# GAN_Synchronous_Buck.net
KiCad netlist of a schematic drawn in Altium Designer
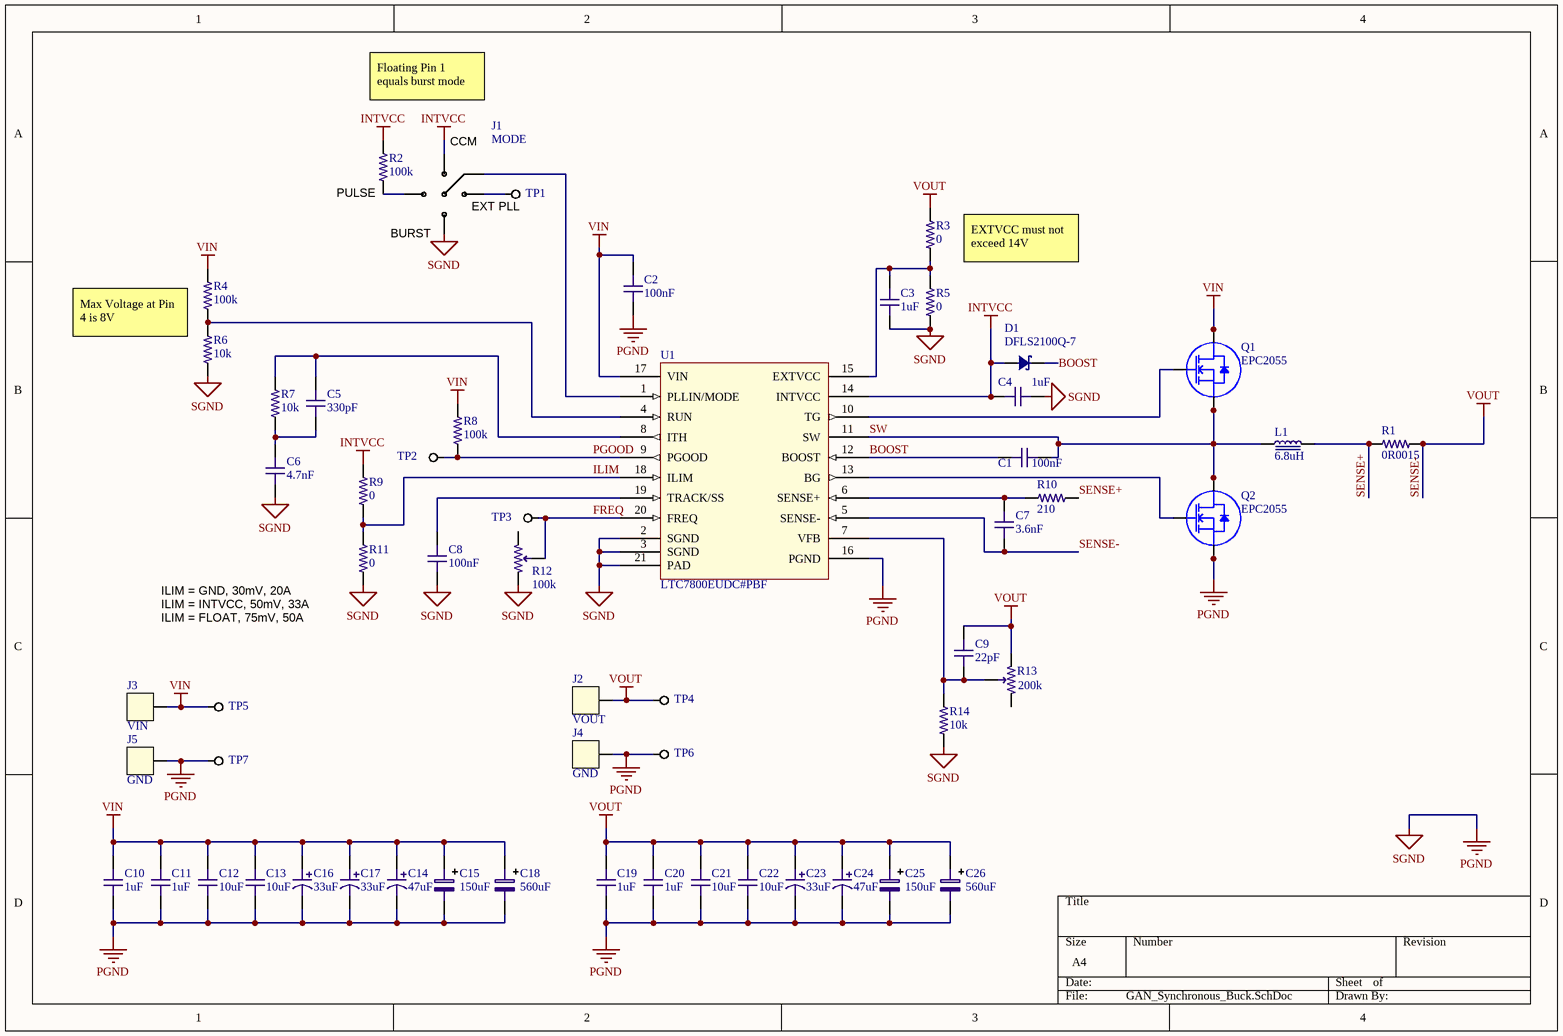
[diagram p0: GAN_Synchronous_Buck.SchDoc]

(export (version "E")
  (design (tool "Eeschema 10.0.6"))
  (components
    (comp (ref "C1")
      (value "100nF")
      (footprint "C0603-IPC")
      (description "CAP CER 0.1UF 50V X7R 0603")
      (fields (field (name "Comment") "C0603 100nF 50V X7R"))
      (libsource (lib "Capacitors") (part "C0603 100nF 50V X7R"))
    )
    (comp (ref "C2")
      (value "100nF")
      (footprint "C0603-IPC")
      (description "CAP CER 0.1UF 50V X7R 0603")
      (fields (field (name "Comment") "C0603 100nF 50V X7R"))
      (libsource (lib "Capacitors") (part "C0603 100nF 50V X7R"))
    )
    (comp (ref "C3")
      (value "1uF")
      (footprint "C0603-IPC")
      (description "CAP CER 1UF 50V X7R 0603")
      (fields (field (name "Comment") "C0603 1uF 50V X7R"))
      (libsource (lib "Capacitors") (part "C0603 1uF 50V X7R"))
    )
    (comp (ref "C4")
      (value "1uF")
      (footprint "C0603-IPC")
      (description "CAP CER 1UF 50V X7R 0603")
      (fields (field (name "Comment") "C0603 1uF 50V X7R"))
      (libsource (lib "Capacitors") (part "C0603 1uF 50V X7R"))
    )
    (comp (ref "C5")
      (value "330pF")
      (footprint "C0603-IPC")
      (description "CAP CER 330PF 50V C0G/NP0 0603")
      (fields (field (name "Comment") "C0603 330pF 50V C0G"))
      (libsource (lib "Capacitors") (part "C0603 330pF 50V C0G"))
    )
    (comp (ref "C6")
      (value "4.7nF")
      (footprint "C0603-IPC")
      (description "CAP CER 4700PF 50V X7R 0603")
      (fields (field (name "Comment") "C0603 4.7nF 50V X7R"))
      (libsource (lib "Capacitors") (part "C0603 4.7nF 50V X7R"))
    )
    (comp (ref "C7")
      (value "3.6nF")
      (footprint "C0603-IPC")
      (description "Chip Capacitor, 0603, 3.6nF, 50V, X7R")
      (fields (field (name "Comment") "C0603 3.6nF 50V C0G"))
      (libsource (lib "Capacitors") (part "C0603 3.6nF 50V C0G"))
    )
    (comp (ref "C8")
      (value "100nF")
      (footprint "C0603-IPC")
      (description "CAP CER 0.1UF 50V X7R 0603")
      (fields (field (name "Comment") "C0603 100nF 50V X7R"))
      (libsource (lib "Capacitors") (part "C0603 100nF 50V X7R"))
    )
    (comp (ref "C9")
      (value "22pF")
      (footprint "C0603-IPC")
      (description "CAP CER 22PF 50V C0G/NP0 0603")
      (fields (field (name "Comment") "C0603 22pF 50V C0G"))
      (libsource (lib "Capacitors") (part "C0603 22pF 50V C0G"))
    )
    (comp (ref "C10")
      (value "1uF")
      (footprint "C0603-IPC")
      (description "CAP CER 1UF 50V X7R 0603")
      (fields (field (name "Comment") "C0603 1uF 50V X7R"))
      (libsource (lib "Capacitors") (part "C0603 1uF 50V X7R"))
    )
    (comp (ref "C11")
      (value "1uF")
      (footprint "C0603-IPC")
      (description "CAP CER 1UF 50V X7R 0603")
      (fields (field (name "Comment") "C0603 1uF 50V X7R"))
      (libsource (lib "Capacitors") (part "C0603 1uF 50V X7R"))
    )
    (comp (ref "C12")
      (value "10uF")
      (footprint "C1210-IPC")
      (description "Chip Capacitor, 1210, 10uF, 75V, X5R")
      (fields (field (name "Comment") "C1210 10uF 75V X5R"))
      (libsource (lib "Capacitors") (part "C1210 10uF 16V X5R"))
    )
    (comp (ref "C13")
      (value "10uF")
      (footprint "C1210-IPC")
      (description "Chip Capacitor, 1210, 10uF, 75V, X5R")
      (fields (field (name "Comment") "C1210 10uF 75V X5R"))
      (libsource (lib "Capacitors") (part "C1210 10uF 16V X5R"))
    )
    (comp (ref "C14")
      (value "47uF")
      (footprint "C-SMD-Polarized-6.3x7.7mm")
      (description "47uF ±20% 50V SMD,6.3x7.7mm Aluminum Electrolytic Capacitors - SMD")
      (fields (field (name "Comment") "UUR1H470MCL6GS"))
      (libsource (lib "Capacitors") (part "C-SMD 47uF 50V Electrolytic"))
    )
    (comp (ref "C15")
      (value "150uF")
      (footprint "C-POLARIZED-5-12.5")
      (fields (field (name "Comment") "35ZLH1000MEFC12.5X20"))
      (libsource (lib "Capacitors") (part "C-THT 1000uF 35V Electrolytic"))
    )
    (comp (ref "C16")
      (value "33uF")
      (footprint "C-SMD-Polarized-10x10.2mm")
      (description "33 µF 80 V Aluminum Electrolytic Capacitors Radial, Can - SMD 1Ohm @ 100kHz 2000 Hrs @ 125°C")
      (fields (field (name "VOLTAGE") "80V") (field (name "Comment") "PCE3675CT-ND"))
      (libsource (lib "Capacitors") (part "C-SMD 33uF 80V Electrolytic"))
    )
    (comp (ref "C17")
      (value "33uF")
      (footprint "C-SMD-Polarized-10x10.2mm")
      (description "33 µF 80 V Aluminum Electrolytic Capacitors Radial, Can - SMD 1Ohm @ 100kHz 2000 Hrs @ 125°C")
      (fields (field (name "VOLTAGE") "80V") (field (name "Comment") "PCE3675CT-ND"))
      (libsource (lib "Capacitors") (part "C-SMD 33uF 80V Electrolytic"))
    )
    (comp (ref "C18")
      (value "560uF")
      (footprint "C-POLARIZED-5-12.5")
      (fields (field (name "Comment") "35ZLH1000MEFC12.5X20"))
      (libsource (lib "Capacitors") (part "C-THT 1000uF 35V Electrolytic"))
    )
    (comp (ref "C19")
      (value "1uF")
      (footprint "C0603-IPC")
      (description "CAP CER 1UF 50V X7R 0603")
      (fields (field (name "Comment") "C0603 1uF 50V X7R"))
      (libsource (lib "Capacitors") (part "C0603 1uF 50V X7R"))
    )
    (comp (ref "C20")
      (value "1uF")
      (footprint "C0603-IPC")
      (description "CAP CER 1UF 50V X7R 0603")
      (fields (field (name "Comment") "C0603 1uF 50V X7R"))
      (libsource (lib "Capacitors") (part "C0603 1uF 50V X7R"))
    )
    (comp (ref "C21")
      (value "10uF")
      (footprint "C1210-IPC")
      (description "Chip Capacitor, 1210, 10uF, 75V, X5R")
      (fields (field (name "Comment") "C1210 10uF 75V X5R"))
      (libsource (lib "Capacitors") (part "C1210 10uF 16V X5R"))
    )
    (comp (ref "C22")
      (value "10uF")
      (footprint "C1210-IPC")
      (description "Chip Capacitor, 1210, 10uF, 75V, X5R")
      (fields (field (name "Comment") "C1210 10uF 75V X5R"))
      (libsource (lib "Capacitors") (part "C1210 10uF 16V X5R"))
    )
    (comp (ref "C23")
      (value "33uF")
      (footprint "C-SMD-Polarized-10x10.2mm")
      (description "33 µF 80 V Aluminum Electrolytic Capacitors Radial, Can - SMD 1Ohm @ 100kHz 2000 Hrs @ 125°C")
      (fields (field (name "VOLTAGE") "80V") (field (name "Comment") "PCE3675CT-ND"))
      (libsource (lib "Capacitors") (part "C-SMD 33uF 80V Electrolytic"))
    )
    (comp (ref "C24")
      (value "47uF")
      (footprint "C-SMD-Polarized-6.3x7.7mm")
      (description "47uF ±20% 50V SMD,6.3x7.7mm Aluminum Electrolytic Capacitors - SMD")
      (fields (field (name "Comment") "UUR1H470MCL6GS"))
      (libsource (lib "Capacitors") (part "C-SMD 47uF 50V Electrolytic"))
    )
    (comp (ref "C25")
      (value "150uF")
      (footprint "C-POLARIZED-5-12.5")
      (fields (field (name "Comment") "35ZLH1000MEFC12.5X20"))
      (libsource (lib "Capacitors") (part "C-THT 1000uF 35V Electrolytic"))
    )
    (comp (ref "C26")
      (value "560uF")
      (footprint "C-POLARIZED-5-12.5")
      (fields (field (name "Comment") "35ZLH1000MEFC12.5X20"))
      (libsource (lib "Capacitors") (part "C-THT 1000uF 35V Electrolytic"))
    )
    (comp (ref "D1")
      (value "DFLS2100Q-7")
      (footprint "POWERDI 123")
      (description "DIODE SCHOTTKY 100V POWERDI123")
      (libsource (lib "Diodes") (part "DFLS1100-7"))
    )
    (comp (ref "J1")
      (value "MODE")
      (footprint "4P Jumper")
      (description "0603 4 Way Solder Jumper")
      (libsource (lib "Switches") (part "4P Jumper"))
    )
    (comp (ref "J2")
      (value "VOUT")
      (footprint "Banana Jack")
      (description "JACK NON-INSULATED .350\"")
      (libsource (lib "Connectors") (part "Banana Jack"))
    )
    (comp (ref "J3")
      (value "VIN")
      (footprint "Banana Jack")
      (description "JACK NON-INSULATED .350\"")
      (libsource (lib "Connectors") (part "Banana Jack"))
    )
    (comp (ref "J4")
      (value "GND")
      (footprint "Banana Jack")
      (description "JACK NON-INSULATED .350\"")
      (libsource (lib "Connectors") (part "Banana Jack"))
    )
    (comp (ref "J5")
      (value "GND")
      (footprint "Banana Jack")
      (description "JACK NON-INSULATED .350\"")
      (libsource (lib "Connectors") (part "Banana Jack"))
    )
    (comp (ref "L1")
      (value "6.8uH")
      (footprint "PQ2614BLA/BHA Bourns")
      (description "FIXED IND 6.8UH 30A 1.6 MOHM SMD")
      (fields (field (name "Comment") "PQ2614BLA-6R8K"))
      (libsource (lib "Inductors") (part "Bourns PQ2614BLA-6R8K"))
    )
    (comp (ref "Q1")
      (value "EPC2055")
      (footprint "D0133CT44M")
      (description "GANFET N-CH 40V 29A 3.6mOhm")
      (fields (field (name "MFG") "EPC"))
      (libsource (lib "Transistors") (part "EPC2055"))
    )
    (comp (ref "Q2")
      (value "EPC2055")
      (footprint "D0133CT44M")
      (description "GANFET N-CH 40V 29A 3.6mOhm")
      (fields (field (name "MFG") "EPC"))
      (libsource (lib "Transistors") (part "EPC2055"))
    )
    (comp (ref "R1")
      (value "0R0015")
      (footprint "R2512-IPC")
      (description "RES SHUNT, 2512, 0.0015 OHM, 1%,")
      (fields (field (name "Comment") "ERJ-M1WTF1M5U"))
      (libsource (lib "Resistors") (part "R0805 0R0015 1%"))
    )
    (comp (ref "R2")
      (value "100k")
      (footprint "R0603-IPC")
      (description "RES SMD 100K OHM 1% 1/10W 0603")
      (fields (field (name "Comment") "R0603 100K 1%"))
      (libsource (lib "Resistors") (part "R0603 100K 1%"))
    )
    (comp (ref "R3")
      (value "0")
      (footprint "R0603-IPC")
      (description "RES SMD 0 OHM JUMPER 1/10W 0603")
      (fields (field (name "Comment") "R0603 0"))
      (libsource (lib "Resistors") (part "R0603 0"))
    )
    (comp (ref "R4")
      (value "100k")
      (footprint "R0603-IPC")
      (description "RES SMD 100K OHM 1% 1/10W 0603")
      (fields (field (name "Comment") "R0603 100K 1%"))
      (libsource (lib "Resistors") (part "R0603 100K 1%"))
    )
    (comp (ref "R5")
      (value "0")
      (footprint "R0603-IPC")
      (description "RES SMD 0 OHM JUMPER 1/10W 0603")
      (fields (field (name "Comment") "R0603 0"))
      (libsource (lib "Resistors") (part "R0603 0"))
    )
    (comp (ref "R6")
      (value "10k")
      (footprint "R0603-IPC-10K")
      (description "RES SMD 10K OHM 1% 1/10W 0603")
      (fields (field (name "Comment") "R0603 10K 1%"))
      (libsource (lib "Resistors") (part "R0603 10K 1%"))
    )
    (comp (ref "R7")
      (value "10k")
      (footprint "R0603-IPC-10K")
      (description "RES SMD 10K OHM 1% 1/10W 0603")
      (fields (field (name "Comment") "R0603 10K 1%"))
      (libsource (lib "Resistors") (part "R0603 10K 1%"))
    )
    (comp (ref "R8")
      (value "100k")
      (footprint "R0603-IPC")
      (description "RES SMD 100K OHM 1% 1/10W 0603")
      (fields (field (name "Comment") "R0603 100K 1%"))
      (libsource (lib "Resistors") (part "R0603 100K 1%"))
    )
    (comp (ref "R9")
      (value "0")
      (footprint "R0603-IPC")
      (description "RES SMD 0 OHM JUMPER 1/10W 0603")
      (fields (field (name "Comment") "R0603 0"))
      (libsource (lib "Resistors") (part "R0603 0"))
    )
    (comp (ref "R10")
      (value "210")
      (footprint "R0603-IPC")
      (description "RES 210 OHM 1% 1/10W 0603")
      (fields (field (name "Comment") "R0603 210R 1%"))
      (libsource (lib "Resistors") (part "R0603 210R 1%"))
    )
    (comp (ref "R11")
      (value "0")
      (footprint "R0603-IPC")
      (description "RES SMD 0 OHM JUMPER 1/10W 0603")
      (fields (field (name "Comment") "R0603 0"))
      (libsource (lib "Resistors") (part "R0603 0"))
    )
    (comp (ref "R12")
      (value "100k")
      (footprint "POT4.8-3.5")
      (description "200 kOhms 0.25W, 1/4W J Lead Surface Mount Trimmer Potentiometer Cermet 5.0 Turn Side Adjustment")
      (fields (field (name "Comment") "FREQ"))
      (libsource (lib "Resistors") (part "Trimmer 200k"))
    )
    (comp (ref "R13")
      (value "200k")
      (footprint "POT4.8-3.5")
      (description "200 kOhms 0.25W, 1/4W J Lead Surface Mount Trimmer Potentiometer Cermet 5.0 Turn Side Adjustment")
      (fields (field (name "Comment") "VOLTAGE"))
      (libsource (lib "Resistors") (part "Trimmer 200k"))
    )
    (comp (ref "R14")
      (value "10k")
      (footprint "R0603-IPC-10K")
      (description "RES SMD 10K OHM 1% 1/10W 0603")
      (fields (field (name "Comment") "R0603 10K 1%"))
      (libsource (lib "Resistors") (part "R0603 10K 1%"))
    )
    (comp (ref "TP1")
      (value "EXT_PLL")
      (footprint "Testpoint_TH")
      (description "Through-hole testpoint hook")
      (libsource (lib "Virtual Parts") (part "Testpoint_TH"))
    )
    (comp (ref "TP2")
      (value "PGOOD")
      (footprint "Testpoint_TH")
      (description "Through-hole testpoint hook")
      (libsource (lib "Virtual Parts") (part "Testpoint_TH"))
    )
    (comp (ref "TP3")
      (value "FREQ")
      (footprint "Testpoint_TH")
      (description "Through-hole testpoint hook")
      (libsource (lib "Virtual Parts") (part "Testpoint_TH"))
    )
    (comp (ref "TP4")
      (value "VOUT")
      (footprint "Testpoint_TH")
      (description "Through-hole testpoint hook")
      (libsource (lib "Virtual Parts") (part "Testpoint_TH"))
    )
    (comp (ref "TP5")
      (value "VIN")
      (footprint "Testpoint_TH")
      (description "Through-hole testpoint hook")
      (libsource (lib "Virtual Parts") (part "Testpoint_TH"))
    )
    (comp (ref "TP6")
      (value "GND")
      (footprint "Testpoint_TH")
      (description "Through-hole testpoint hook")
      (libsource (lib "Virtual Parts") (part "Testpoint_TH"))
    )
    (comp (ref "TP7")
      (value "GND")
      (footprint "Testpoint_TH")
      (description "Through-hole testpoint hook")
      (libsource (lib "Virtual Parts") (part "Testpoint_TH"))
    )
    (comp (ref "U1")
      (value "LTC7800EUDC#PBF")
      (footprint "QFN20 - 3x4MM - ADI")
      (description "Synchrnous Buck Regulator Positive Output Step-Down - DC-DC Controller IC 20-QFN (3x4)")
      (libsource (lib "Integrated Circuits") (part "LTC7800EUDC"))
    )
  )
  (nets
    (net (code "1") (name "/BOOST") (class "Default")
      (node (ref "C1") (pin "1") (pintype "passive"))
      (node (ref "D1") (pin "1") (pinfunction "1_1") (pintype "passive"))
      (node (ref "U1") (pin "12") (pinfunction "BOOST_12") (pintype "input"))
    )
    (net (code "2") (name "/FREQ") (class "Default")
      (node (ref "R12") (pin "2") (pinfunction "W_2") (pintype "passive"))
      (node (ref "TP3") (pin "1") (pinfunction "1_1") (pintype "passive"))
      (node (ref "U1") (pin "20") (pinfunction "FREQ_20") (pintype "input"))
    )
    (net (code "3") (name "/ILIM") (class "Default")
      (node (ref "R11") (pin "2") (pintype "passive"))
      (node (ref "R9") (pin "1") (pintype "passive"))
      (node (ref "U1") (pin "18") (pinfunction "ILIM_18") (pintype "input"))
    )
    (net (code "4") (name "/PGOOD") (class "Default")
      (node (ref "R8") (pin "1") (pintype "passive"))
      (node (ref "TP2") (pin "1") (pinfunction "1_1") (pintype "passive"))
      (node (ref "U1") (pin "9") (pinfunction "PGOOD_9") (pintype "output"))
    )
    (net (code "5") (name "/SENSE+") (class "Default")
      (node (ref "L1") (pin "2") (pintype "passive"))
      (node (ref "R1") (pin "1") (pintype "passive"))
      (node (ref "R10") (pin "1") (pintype "passive"))
    )
    (net (code "6") (name "/SW") (class "Default")
      (node (ref "C1") (pin "2") (pintype "passive"))
      (node (ref "L1") (pin "1") (pintype "passive"))
      (node (ref "Q1") (pin "2") (pinfunction "S_2") (pintype "open_emitter"))
      (node (ref "Q1") (pin "4") (pinfunction "S_4") (pintype "open_emitter"))
      (node (ref "Q1") (pin "6") (pinfunction "S_6") (pintype "open_emitter"))
      (node (ref "Q2") (pin "3") (pinfunction "D_3") (pintype "open_collector"))
      (node (ref "Q2") (pin "5") (pinfunction "D_5") (pintype "open_collector"))
      (node (ref "U1") (pin "11") (pinfunction "SW_11") (pintype "tri_state"))
    )
    (net (code "7") (name "INTVCC") (class "Default")
      (node (ref "C4") (pin "1") (pintype "passive"))
      (node (ref "D1") (pin "2") (pinfunction "2_2") (pintype "passive"))
      (node (ref "J1") (pin "1") (pinfunction "1_1") (pintype "passive"))
      (node (ref "R2") (pin "2") (pintype "passive"))
      (node (ref "R9") (pin "2") (pintype "passive"))
      (node (ref "U1") (pin "14") (pinfunction "INTVCC_14") (pintype "power_in"))
    )
    (net (code "8") (name "Net-(C5-Pad1)") (class "Default")
      (node (ref "C5") (pin "1") (pintype "passive"))
      (node (ref "C6") (pin "2") (pintype "passive"))
      (node (ref "R7") (pin "1") (pintype "passive"))
    )
    (net (code "9") (name "Net-(J1-Pad2)") (class "Default")
      (node (ref "J1") (pin "2") (pinfunction "2_2") (pintype "passive"))
      (node (ref "TP1") (pin "1") (pinfunction "1_1") (pintype "passive"))
    )
    (net (code "10") (name "Net-(J1-Pad4)") (class "Default")
      (node (ref "J1") (pin "4") (pinfunction "4_4") (pintype "passive"))
      (node (ref "R2") (pin "1") (pintype "passive"))
    )
    (net (code "11") (name "Net-(Q1-G)") (class "Default")
      (node (ref "Q1") (pin "1") (pinfunction "G_1") (pintype "passive"))
      (node (ref "U1") (pin "10") (pinfunction "TG_10") (pintype "output"))
    )
    (net (code "12") (name "Net-(Q2-G)") (class "Default")
      (node (ref "Q2") (pin "1") (pinfunction "G_1") (pintype "passive"))
      (node (ref "U1") (pin "13") (pinfunction "BG_13") (pintype "output"))
    )
    (net (code "13") (name "Net-(R13-W)") (class "Default")
      (node (ref "C9") (pin "1") (pintype "passive"))
      (node (ref "R13") (pin "2") (pinfunction "W_2") (pintype "passive"))
      (node (ref "R14") (pin "2") (pintype "passive"))
      (node (ref "U1") (pin "7") (pinfunction "VFB_7") (pintype "tri_state"))
    )
    (net (code "14") (name "Net-(U1-EXTVCC)") (class "Default")
      (node (ref "C3") (pin "2") (pintype "passive"))
      (node (ref "R3") (pin "1") (pintype "passive"))
      (node (ref "R5") (pin "2") (pintype "passive"))
      (node (ref "U1") (pin "15") (pinfunction "EXTVCC_15") (pintype "power_in"))
    )
    (net (code "15") (name "Net-(U1-ITH)") (class "Default")
      (node (ref "C5") (pin "2") (pintype "passive"))
      (node (ref "R7") (pin "2") (pintype "passive"))
      (node (ref "U1") (pin "8") (pinfunction "ITH_8") (pintype "output"))
    )
    (net (code "16") (name "Net-(U1-PLLIN{slash}MODE)") (class "Default")
      (node (ref "J1") (pin "5") (pinfunction "5_5") (pintype "passive"))
      (node (ref "U1") (pin "1") (pinfunction "PLLIN/MODE_1") (pintype "input"))
    )
    (net (code "17") (name "Net-(U1-RUN)") (class "Default")
      (node (ref "R4") (pin "1") (pintype "passive"))
      (node (ref "R6") (pin "2") (pintype "passive"))
      (node (ref "U1") (pin "4") (pinfunction "RUN_4") (pintype "input"))
    )
    (net (code "18") (name "Net-(U1-SENSE+)") (class "Default")
      (node (ref "C7") (pin "2") (pintype "passive"))
      (node (ref "R10") (pin "2") (pintype "passive"))
      (node (ref "U1") (pin "6") (pinfunction "SENSE+_6") (pintype "input"))
    )
    (net (code "19") (name "Net-(U1-TRACK{slash}SS)") (class "Default")
      (node (ref "C8") (pin "2") (pintype "passive"))
      (node (ref "U1") (pin "19") (pinfunction "TRACK/SS_19") (pintype "input"))
    )
    (net (code "20") (name "PGND") (class "Default")
      (node (ref "C10") (pin "1") (pintype "passive"))
      (node (ref "C11") (pin "1") (pintype "passive"))
      (node (ref "C12") (pin "1") (pintype "passive"))
      (node (ref "C13") (pin "1") (pintype "passive"))
      (node (ref "C14") (pin "2") (pintype "passive"))
      (node (ref "C15") (pin "2") (pintype "passive"))
      (node (ref "C16") (pin "2") (pintype "passive"))
      (node (ref "C17") (pin "2") (pintype "passive"))
      (node (ref "C18") (pin "2") (pintype "passive"))
      (node (ref "C19") (pin "1") (pintype "passive"))
      (node (ref "C2") (pin "2") (pintype "passive"))
      (node (ref "C20") (pin "1") (pintype "passive"))
      (node (ref "C21") (pin "1") (pintype "passive"))
      (node (ref "C22") (pin "1") (pintype "passive"))
      (node (ref "C23") (pin "2") (pintype "passive"))
      (node (ref "C24") (pin "2") (pintype "passive"))
      (node (ref "C25") (pin "2") (pintype "passive"))
      (node (ref "C26") (pin "2") (pintype "passive"))
      (node (ref "C3") (pin "1") (pintype "passive"))
      (node (ref "C4") (pin "2") (pintype "passive"))
      (node (ref "C6") (pin "1") (pintype "passive"))
      (node (ref "C8") (pin "1") (pintype "passive"))
      (node (ref "J1") (pin "3") (pinfunction "3_3") (pintype "passive"))
      (node (ref "J4") (pin "1") (pinfunction "1_1") (pintype "passive"))
      (node (ref "J5") (pin "1") (pinfunction "1_1") (pintype "passive"))
      (node (ref "Q2") (pin "2") (pinfunction "S_2") (pintype "open_emitter"))
      (node (ref "Q2") (pin "4") (pinfunction "S_4") (pintype "open_emitter"))
      (node (ref "Q2") (pin "6") (pinfunction "S_6") (pintype "open_emitter"))
      (node (ref "R11") (pin "1") (pintype "passive"))
      (node (ref "R12") (pin "1") (pintype "passive"))
      (node (ref "R14") (pin "1") (pintype "passive"))
      (node (ref "R5") (pin "1") (pintype "passive"))
      (node (ref "R6") (pin "1") (pintype "passive"))
      (node (ref "TP6") (pin "1") (pinfunction "1_1") (pintype "passive"))
      (node (ref "TP7") (pin "1") (pinfunction "1_1") (pintype "passive"))
      (node (ref "U1") (pin "16") (pinfunction "PGND_16") (pintype "power_in"))
      (node (ref "U1") (pin "2") (pinfunction "SGND_2") (pintype "power_in"))
      (node (ref "U1") (pin "21") (pinfunction "PAD_21") (pintype "power_in"))
      (node (ref "U1") (pin "3") (pinfunction "SGND_3") (pintype "power_in"))
    )
    (net (code "21") (name "VIN") (class "Default")
      (node (ref "C10") (pin "2") (pintype "passive"))
      (node (ref "C11") (pin "2") (pintype "passive"))
      (node (ref "C12") (pin "2") (pintype "passive"))
      (node (ref "C13") (pin "2") (pintype "passive"))
      (node (ref "C14") (pin "1") (pintype "passive"))
      (node (ref "C15") (pin "1") (pintype "passive"))
      (node (ref "C16") (pin "1") (pintype "passive"))
      (node (ref "C17") (pin "1") (pintype "passive"))
      (node (ref "C18") (pin "1") (pintype "passive"))
      (node (ref "C2") (pin "1") (pintype "passive"))
      (node (ref "J3") (pin "1") (pinfunction "1_1") (pintype "passive"))
      (node (ref "Q1") (pin "3") (pinfunction "D_3") (pintype "open_collector"))
      (node (ref "Q1") (pin "5") (pinfunction "D_5") (pintype "open_collector"))
      (node (ref "R4") (pin "2") (pintype "passive"))
      (node (ref "R8") (pin "2") (pintype "passive"))
      (node (ref "TP5") (pin "1") (pinfunction "1_1") (pintype "passive"))
      (node (ref "U1") (pin "17") (pinfunction "VIN_17") (pintype "power_in"))
    )
    (net (code "22") (name "VOUT") (class "Default")
      (node (ref "C19") (pin "2") (pintype "passive"))
      (node (ref "C20") (pin "2") (pintype "passive"))
      (node (ref "C21") (pin "2") (pintype "passive"))
      (node (ref "C22") (pin "2") (pintype "passive"))
      (node (ref "C23") (pin "1") (pintype "passive"))
      (node (ref "C24") (pin "1") (pintype "passive"))
      (node (ref "C25") (pin "1") (pintype "passive"))
      (node (ref "C26") (pin "1") (pintype "passive"))
      (node (ref "C7") (pin "1") (pintype "passive"))
      (node (ref "C9") (pin "2") (pintype "passive"))
      (node (ref "J2") (pin "1") (pinfunction "1_1") (pintype "passive"))
      (node (ref "R1") (pin "2") (pintype "passive"))
      (node (ref "R13") (pin "1") (pintype "passive"))
      (node (ref "R3") (pin "2") (pintype "passive"))
      (node (ref "TP4") (pin "1") (pinfunction "1_1") (pintype "passive"))
      (node (ref "U1") (pin "5") (pinfunction "SENSE-_5") (pintype "input"))
    )
    (net (code "23") (name "unconnected-(R12-Pad3)") (class "Default")
      (node (ref "R12") (pin "3") (pintype "passive"))
    )
    (net (code "24") (name "unconnected-(R13-Pad3)") (class "Default")
      (node (ref "R13") (pin "3") (pintype "passive"))
    )
  )
)
